# shinobi_BLE.net
KiCad netlist of a schematic drawn in EAGLE
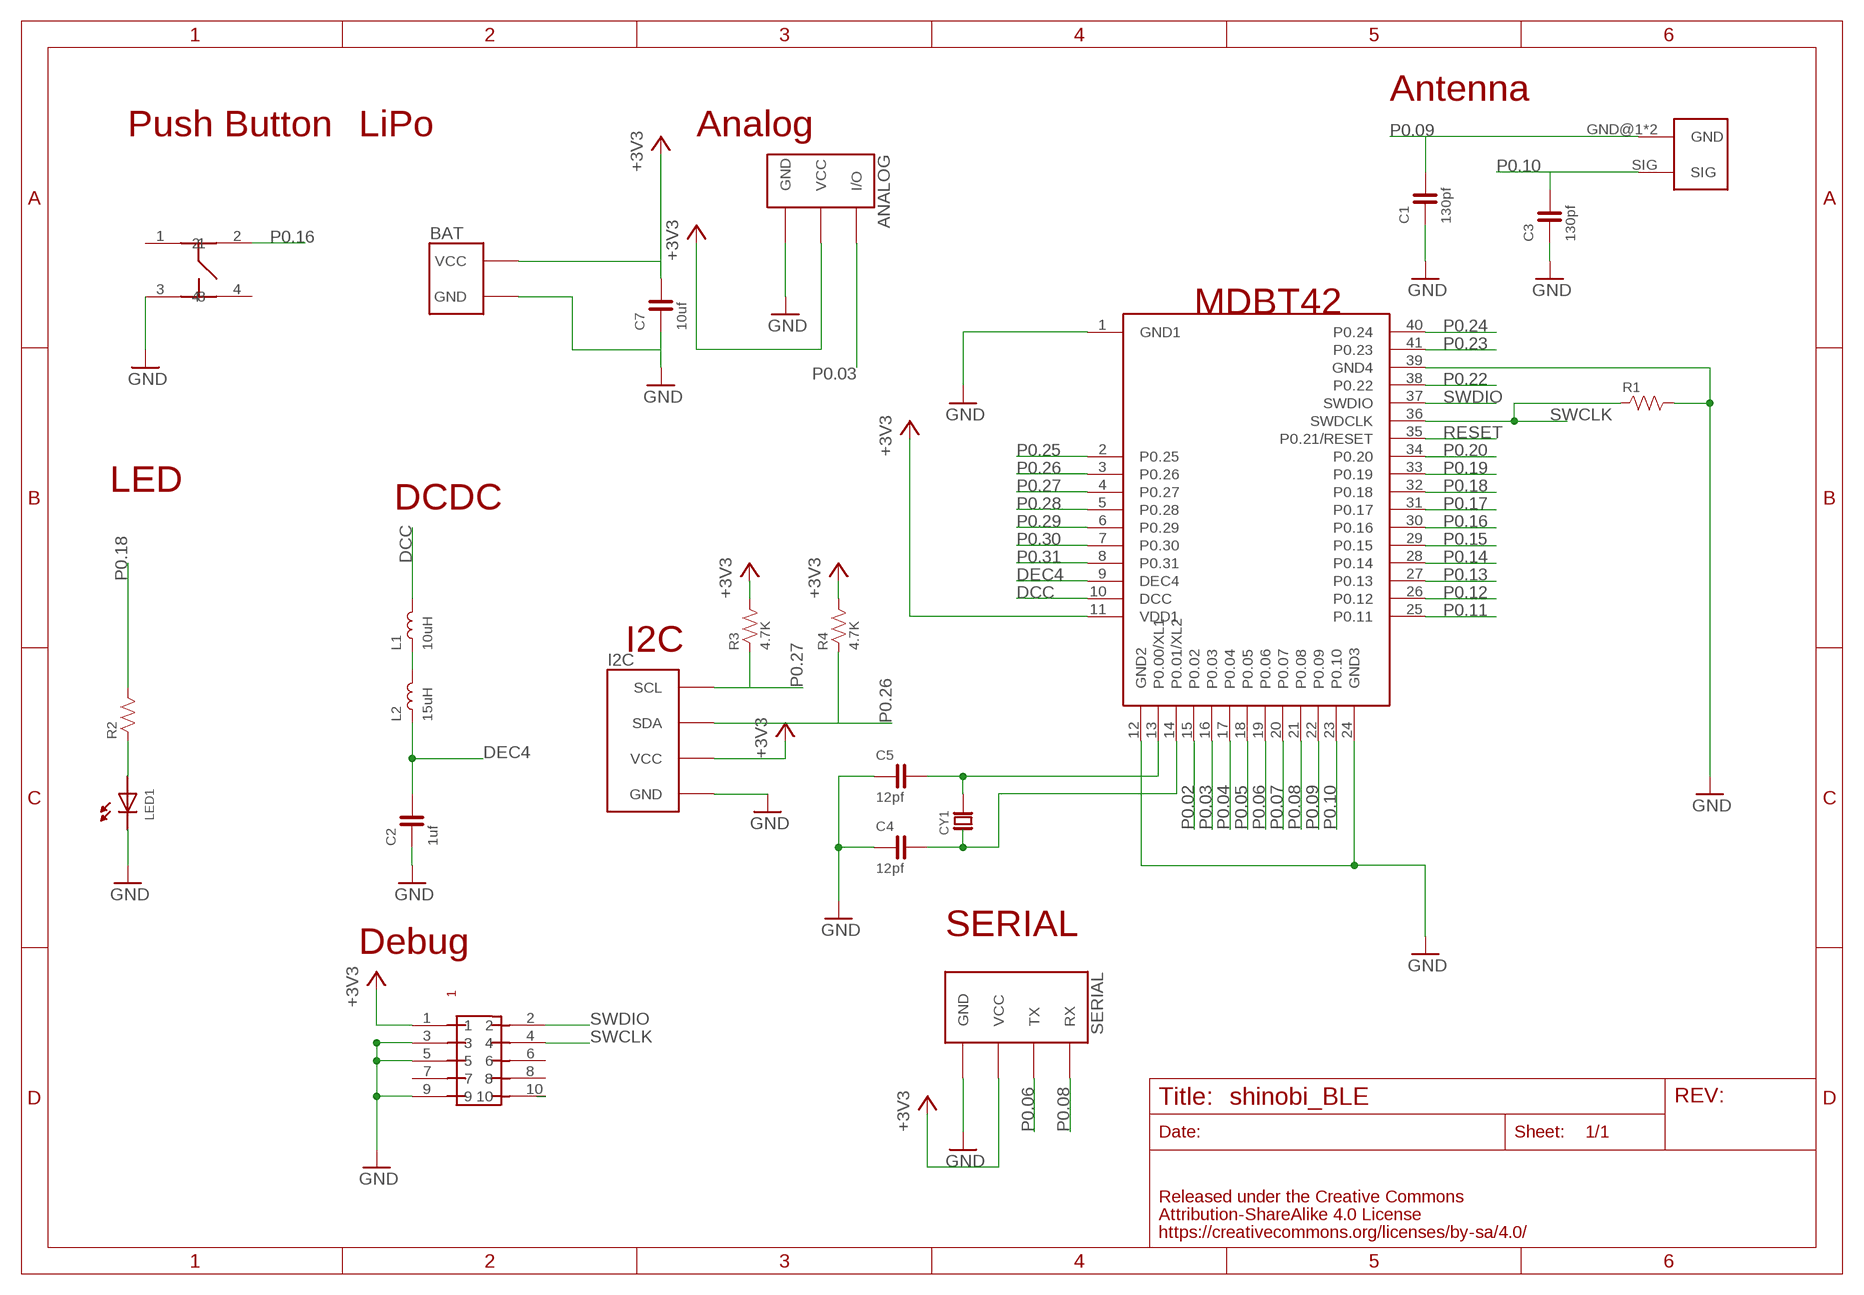
[diagram p0: schematic, sheet 1]

(export (version "E")
  (design (tool "Eeschema 10.0.6"))
  (components
    (comp (ref "ANALOG")
      (value "FABO_BRICK_3PIN-S03B-PASK-2_LONG")
      (footprint "eagle-import:FABO_BRICK_3PIN_S03B-PASK-2_LONG")
      (libsource (lib "eagle-import") (part "FABO_BRICK_3PIN-S03B-PASK-2_LONG"))
    )
    (comp (ref "BAT")
      (value "FABO_BRICK_2PIN_SIDE")
      (footprint "eagle-import:FABO_BRICK_2PIN_S02B−PASK-2_SILK")
      (libsource (lib "eagle-import") (part "FABO_BRICK_2PIN_SIDE"))
    )
    (comp (ref "C1")
      (value "130pf")
      (footprint "eagle-import:0603")
      (libsource (lib "eagle-import") (part "CAPACITOR-0603"))
    )
    (comp (ref "C2")
      (value "1uf")
      (footprint "eagle-import:0603")
      (libsource (lib "eagle-import") (part "CAPACITOR-0603"))
    )
    (comp (ref "C3")
      (value "130pf")
      (footprint "eagle-import:0603")
      (libsource (lib "eagle-import") (part "CAPACITOR-0603"))
    )
    (comp (ref "C4")
      (value "12pf")
      (footprint "eagle-import:0603")
      (libsource (lib "eagle-import") (part "CAPACITOR-0603"))
    )
    (comp (ref "C5")
      (value "12pf")
      (footprint "eagle-import:0603")
      (libsource (lib "eagle-import") (part "CAPACITOR-0603"))
    )
    (comp (ref "C7")
      (value "10uf")
      (footprint "eagle-import:0603")
      (libsource (lib "eagle-import") (part "CAPACITOR-0603"))
    )
    (comp (ref "CY1")
      (value "CRYSTAL-ABS07")
      (footprint "eagle-import:ABRACON-ABS07-32.768KHZ")
      (libsource (lib "eagle-import") (part "CRYSTAL-ABS07"))
    )
    (comp (ref "I2C")
      (value "FABO_BRICK_I2C-S04B-PASK-2_LONG")
      (footprint "eagle-import:FABO_BRICK_I2C_S04B-PASK-2_LONG")
      (libsource (lib "eagle-import") (part "FABO_BRICK_I2C-S04B-PASK-2_LONG"))
    )
    (comp (ref "L1")
      (value "10uH")
      (footprint "eagle-import:0603")
      (libsource (lib "eagle-import") (part "INDUCTOR-0603"))
    )
    (comp (ref "L2")
      (value "15uH")
      (footprint "eagle-import:1812")
      (libsource (lib "eagle-import") (part "INDUCTOR-1812"))
    )
    (comp (ref "LED1")
      (value "LED-0603")
      (footprint "eagle-import:0603")
      (libsource (lib "eagle-import") (part "LED-0603"))
    )
    (comp (ref "R1")
      (value "RESISTOR-0603")
      (footprint "eagle-import:0603")
      (libsource (lib "eagle-import") (part "RESISTOR-0603"))
    )
    (comp (ref "R2")
      (value "RESISTOR-0603")
      (footprint "eagle-import:0603")
      (libsource (lib "eagle-import") (part "RESISTOR-0603"))
    )
    (comp (ref "R3")
      (value "4.7K")
      (footprint "eagle-import:0603")
      (libsource (lib "eagle-import") (part "RESISTOR-0603"))
    )
    (comp (ref "R4")
      (value "4.7K")
      (footprint "eagle-import:0603")
      (libsource (lib "eagle-import") (part "RESISTOR-0603"))
    )
    (comp (ref "SERIAL")
      (value "FABO_BRICK_SERIAL-S04B-PASK-2_LONG")
      (footprint "eagle-import:FABO_BRICK_SERIAL_S04B-PASK-2_LONG")
      (libsource (lib "eagle-import") (part "FABO_BRICK_SERIAL-S04B-PASK-2_LONG"))
    )
    (comp (ref "U$2")
      (value "RAYTAC-MDBT42")
      (footprint "eagle-import:RAYTAC-MDBT42")
      (libsource (lib "eagle-import") (part "RAYTAC-MDBT42"))
    )
    (comp (ref "U$4")
      (value "PIN-HEADER-SMT(1.27MM)2X5")
      (footprint "eagle-import:PIN-HEADER-SMT(1.27MM)2X5")
      (libsource (lib "eagle-import") (part "PIN-HEADER-SMT(1.27MM)2X5"))
    )
    (comp (ref "U$5")
      (value "SWICTH-4P(KMR2)")
      (footprint "eagle-import:SWITCH-4P(KMR2)")
      (libsource (lib "eagle-import") (part "SWICTH-4P(KMR2)"))
    )
    (comp (ref "UF1")
      (value "HIROSE-U.FL")
      (footprint "eagle-import:HIROSE-UF.L")
      (libsource (lib "eagle-import") (part "HIROSE-U.FL"))
    )
  )
  (nets
    (net (code "1") (name "+3V3") (class "Default")
      (node (ref "ANALOG") (pin "VCC") (pinfunction "VCC_VCC") (pintype "bidirectional"))
      (node (ref "BAT") (pin "VCC") (pinfunction "VCC_VCC") (pintype "bidirectional"))
      (node (ref "C7") (pin "2") (pinfunction "2_2") (pintype "passive"))
      (node (ref "I2C") (pin "VCC") (pinfunction "VCC_VCC") (pintype "bidirectional"))
      (node (ref "R3") (pin "2") (pinfunction "2_2") (pintype "bidirectional"))
      (node (ref "R4") (pin "2") (pinfunction "2_2") (pintype "bidirectional"))
      (node (ref "SERIAL") (pin "VCC") (pinfunction "VCC_VCC") (pintype "bidirectional"))
      (node (ref "U$2") (pin "11") (pinfunction "VDD1_11") (pintype "bidirectional"))
      (node (ref "U$4") (pin "1") (pinfunction "1_1") (pintype "bidirectional"))
    )
    (net (code "2") (name "/DCC") (class "Default")
      (node (ref "L1") (pin "2") (pinfunction "2_2") (pintype "bidirectional"))
      (node (ref "U$2") (pin "10") (pinfunction "DCC_10") (pintype "bidirectional"))
    )
    (net (code "3") (name "/DEC4") (class "Default")
      (node (ref "C2") (pin "2") (pinfunction "2_2") (pintype "passive"))
      (node (ref "L2") (pin "P$1") (pinfunction "1_P$1") (pintype "bidirectional"))
      (node (ref "U$2") (pin "9") (pinfunction "DEC4_9") (pintype "bidirectional"))
    )
    (net (code "4") (name "/P0.02") (class "Default")
      (node (ref "U$2") (pin "15") (pinfunction "P0.02_15") (pintype "bidirectional"))
    )
    (net (code "5") (name "/P0.03") (class "Default")
      (node (ref "ANALOG") (pin "I/O") (pinfunction "I/O_I/O") (pintype "bidirectional"))
      (node (ref "U$2") (pin "16") (pinfunction "P0.03_16") (pintype "bidirectional"))
    )
    (net (code "6") (name "/P0.04") (class "Default")
      (node (ref "U$2") (pin "17") (pinfunction "P0.04_17") (pintype "bidirectional"))
    )
    (net (code "7") (name "/P0.05") (class "Default")
      (node (ref "U$2") (pin "18") (pinfunction "P0.05_18") (pintype "bidirectional"))
    )
    (net (code "8") (name "/P0.06") (class "Default")
      (node (ref "SERIAL") (pin "TX") (pinfunction "TX_TX") (pintype "bidirectional"))
      (node (ref "U$2") (pin "19") (pinfunction "P0.06_19") (pintype "bidirectional"))
    )
    (net (code "9") (name "/P0.07") (class "Default")
      (node (ref "U$2") (pin "20") (pinfunction "P0.07_20") (pintype "bidirectional"))
    )
    (net (code "10") (name "/P0.08") (class "Default")
      (node (ref "SERIAL") (pin "RX") (pinfunction "RX_RX") (pintype "bidirectional"))
      (node (ref "U$2") (pin "21") (pinfunction "P0.08_21") (pintype "bidirectional"))
    )
    (net (code "11") (name "/P0.09") (class "Default")
      (node (ref "C1") (pin "2") (pinfunction "2_2") (pintype "passive"))
      (node (ref "U$2") (pin "22") (pinfunction "P0.09_22") (pintype "bidirectional"))
      (node (ref "UF1") (pin "GND@1") (pinfunction "GND_GND@1") (pintype "bidirectional"))
      (node (ref "UF1") (pin "GND@2") (pinfunction "GND_GND@2") (pintype "bidirectional"))
    )
    (net (code "12") (name "/P0.10") (class "Default")
      (node (ref "C3") (pin "2") (pinfunction "2_2") (pintype "passive"))
      (node (ref "U$2") (pin "23") (pinfunction "P0.10_23") (pintype "bidirectional"))
      (node (ref "UF1") (pin "SIG") (pinfunction "SIG_SIG") (pintype "bidirectional"))
    )
    (net (code "13") (name "/P0.11") (class "Default")
      (node (ref "U$2") (pin "25") (pinfunction "P0.11_25") (pintype "bidirectional"))
    )
    (net (code "14") (name "/P0.12") (class "Default")
      (node (ref "U$2") (pin "26") (pinfunction "P0.12_26") (pintype "bidirectional"))
    )
    (net (code "15") (name "/P0.13") (class "Default")
      (node (ref "U$2") (pin "27") (pinfunction "P0.13_27") (pintype "bidirectional"))
    )
    (net (code "16") (name "/P0.14") (class "Default")
      (node (ref "U$2") (pin "28") (pinfunction "P0.14_28") (pintype "bidirectional"))
    )
    (net (code "17") (name "/P0.15") (class "Default")
      (node (ref "U$2") (pin "29") (pinfunction "P0.15_29") (pintype "bidirectional"))
    )
    (net (code "18") (name "/P0.16") (class "Default")
      (node (ref "U$2") (pin "30") (pinfunction "P0.16_30") (pintype "bidirectional"))
      (node (ref "U$5") (pin "2") (pinfunction "2_2") (pintype "bidirectional"))
    )
    (net (code "19") (name "/P0.17") (class "Default")
      (node (ref "U$2") (pin "31") (pinfunction "P0.17_31") (pintype "bidirectional"))
    )
    (net (code "20") (name "/P0.18") (class "Default")
      (node (ref "R2") (pin "2") (pinfunction "2_2") (pintype "bidirectional"))
      (node (ref "U$2") (pin "32") (pinfunction "P0.18_32") (pintype "bidirectional"))
    )
    (net (code "21") (name "/P0.19") (class "Default")
      (node (ref "U$2") (pin "33") (pinfunction "P0.19_33") (pintype "bidirectional"))
    )
    (net (code "22") (name "/P0.20") (class "Default")
      (node (ref "U$2") (pin "34") (pinfunction "P0.20_34") (pintype "bidirectional"))
    )
    (net (code "23") (name "/P0.22") (class "Default")
      (node (ref "U$2") (pin "38") (pinfunction "P0.22_38") (pintype "bidirectional"))
    )
    (net (code "24") (name "/P0.23") (class "Default")
      (node (ref "U$2") (pin "41") (pinfunction "P0.23_41") (pintype "bidirectional"))
    )
    (net (code "25") (name "/P0.24") (class "Default")
      (node (ref "U$2") (pin "40") (pinfunction "P0.24_40") (pintype "bidirectional"))
    )
    (net (code "26") (name "/P0.25") (class "Default")
      (node (ref "U$2") (pin "2") (pinfunction "P0.25_2") (pintype "bidirectional"))
    )
    (net (code "27") (name "/P0.26") (class "Default")
      (node (ref "I2C") (pin "SDA") (pinfunction "SDA_SDA") (pintype "bidirectional"))
      (node (ref "R4") (pin "1") (pinfunction "1_1") (pintype "bidirectional"))
      (node (ref "U$2") (pin "3") (pinfunction "P0.26_3") (pintype "bidirectional"))
    )
    (net (code "28") (name "/P0.27") (class "Default")
      (node (ref "I2C") (pin "SCL") (pinfunction "SCL_SCL") (pintype "bidirectional"))
      (node (ref "R3") (pin "1") (pinfunction "1_1") (pintype "bidirectional"))
      (node (ref "U$2") (pin "4") (pinfunction "P0.27_4") (pintype "bidirectional"))
    )
    (net (code "29") (name "/P0.28") (class "Default")
      (node (ref "U$2") (pin "5") (pinfunction "P0.28_5") (pintype "bidirectional"))
    )
    (net (code "30") (name "/P0.29") (class "Default")
      (node (ref "U$2") (pin "6") (pinfunction "P0.29_6") (pintype "bidirectional"))
    )
    (net (code "31") (name "/P0.30") (class "Default")
      (node (ref "U$2") (pin "7") (pinfunction "P0.30_7") (pintype "bidirectional"))
    )
    (net (code "32") (name "/P0.31") (class "Default")
      (node (ref "U$2") (pin "8") (pinfunction "P0.31_8") (pintype "bidirectional"))
    )
    (net (code "33") (name "/RESET") (class "Default")
      (node (ref "U$2") (pin "35") (pinfunction "P0.21/RESET_35") (pintype "bidirectional"))
    )
    (net (code "34") (name "/SWCLK") (class "Default")
      (node (ref "R1") (pin "1") (pinfunction "1_1") (pintype "bidirectional"))
      (node (ref "U$2") (pin "36") (pinfunction "SWDCLK_36") (pintype "bidirectional"))
      (node (ref "U$4") (pin "4") (pinfunction "4_4") (pintype "bidirectional"))
    )
    (net (code "35") (name "/SWDIO") (class "Default")
      (node (ref "U$2") (pin "37") (pinfunction "SWDIO_37") (pintype "bidirectional"))
      (node (ref "U$4") (pin "2") (pinfunction "2_2") (pintype "bidirectional"))
    )
    (net (code "36") (name "GND") (class "Default")
      (node (ref "ANALOG") (pin "GND") (pinfunction "GND_GND") (pintype "bidirectional"))
      (node (ref "BAT") (pin "GND") (pinfunction "GND_GND") (pintype "bidirectional"))
      (node (ref "C1") (pin "1") (pinfunction "1_1") (pintype "passive"))
      (node (ref "C2") (pin "1") (pinfunction "1_1") (pintype "passive"))
      (node (ref "C3") (pin "1") (pinfunction "1_1") (pintype "passive"))
      (node (ref "C4") (pin "1") (pinfunction "1_1") (pintype "passive"))
      (node (ref "C5") (pin "1") (pinfunction "1_1") (pintype "passive"))
      (node (ref "C7") (pin "1") (pinfunction "1_1") (pintype "passive"))
      (node (ref "I2C") (pin "GND") (pinfunction "GND_GND") (pintype "bidirectional"))
      (node (ref "LED1") (pin "CATHODE") (pinfunction "CATHODE_CATHODE") (pintype "passive"))
      (node (ref "R1") (pin "2") (pinfunction "2_2") (pintype "bidirectional"))
      (node (ref "SERIAL") (pin "GND") (pinfunction "GND_GND") (pintype "bidirectional"))
      (node (ref "U$2") (pin "1") (pinfunction "GND1_1") (pintype "bidirectional"))
      (node (ref "U$2") (pin "12") (pinfunction "GND2_12") (pintype "bidirectional"))
      (node (ref "U$2") (pin "24") (pinfunction "GND3_24") (pintype "bidirectional"))
      (node (ref "U$2") (pin "39") (pinfunction "GND4_39") (pintype "bidirectional"))
      (node (ref "U$4") (pin "3") (pinfunction "3_3") (pintype "bidirectional"))
      (node (ref "U$4") (pin "5") (pinfunction "5_5") (pintype "bidirectional"))
      (node (ref "U$4") (pin "9") (pinfunction "9_9") (pintype "bidirectional"))
      (node (ref "U$5") (pin "3") (pinfunction "3_3") (pintype "bidirectional"))
    )
    (net (code "37") (name "Net-(L2-2)") (class "Default")
      (node (ref "L1") (pin "1") (pinfunction "1_1") (pintype "bidirectional"))
      (node (ref "L2") (pin "P$2") (pinfunction "2_P$2") (pintype "bidirectional"))
    )
    (net (code "38") (name "Net-(LED1-PadANODE)") (class "Default")
      (node (ref "LED1") (pin "ANODE") (pinfunction "ANODE_ANODE") (pintype "passive"))
      (node (ref "R2") (pin "1") (pinfunction "1_1") (pintype "bidirectional"))
    )
    (net (code "39") (name "Net-(U$2-P0.00{slash}XL1)") (class "Default")
      (node (ref "C5") (pin "2") (pinfunction "2_2") (pintype "passive"))
      (node (ref "CY1") (pin "P$2") (pinfunction "P$2_P$2") (pintype "bidirectional"))
      (node (ref "U$2") (pin "13") (pinfunction "P0.00/XL1_13") (pintype "bidirectional"))
    )
    (net (code "40") (name "Net-(U$2-P0.01{slash}XL2)") (class "Default")
      (node (ref "C4") (pin "2") (pinfunction "2_2") (pintype "passive"))
      (node (ref "CY1") (pin "P$1") (pinfunction "P$1_P$1") (pintype "bidirectional"))
      (node (ref "U$2") (pin "14") (pinfunction "P0.01/XL2_14") (pintype "bidirectional"))
    )
    (net (code "41") (name "unconnected-(U$4-Pad6)") (class "Default")
      (node (ref "U$4") (pin "6") (pinfunction "6_6") (pintype "bidirectional"))
    )
    (net (code "42") (name "unconnected-(U$4-Pad7)") (class "Default")
      (node (ref "U$4") (pin "7") (pinfunction "7_7") (pintype "bidirectional"))
    )
    (net (code "43") (name "unconnected-(U$4-Pad8)") (class "Default")
      (node (ref "U$4") (pin "8") (pinfunction "8_8") (pintype "bidirectional"))
    )
    (net (code "44") (name "unconnected-(U$4-Pad10)") (class "Default")
      (node (ref "U$4") (pin "10") (pinfunction "10_10") (pintype "bidirectional"))
    )
    (net (code "45") (name "unconnected-(U$5-Pad1)") (class "Default")
      (node (ref "U$5") (pin "1") (pinfunction "1_1") (pintype "bidirectional"))
    )
    (net (code "46") (name "unconnected-(U$5-Pad4)") (class "Default")
      (node (ref "U$5") (pin "4") (pinfunction "4_4") (pintype "bidirectional"))
    )
  )
)
